# 2_-Input.net
KiCad netlist of a schematic drawn in Altium Designer
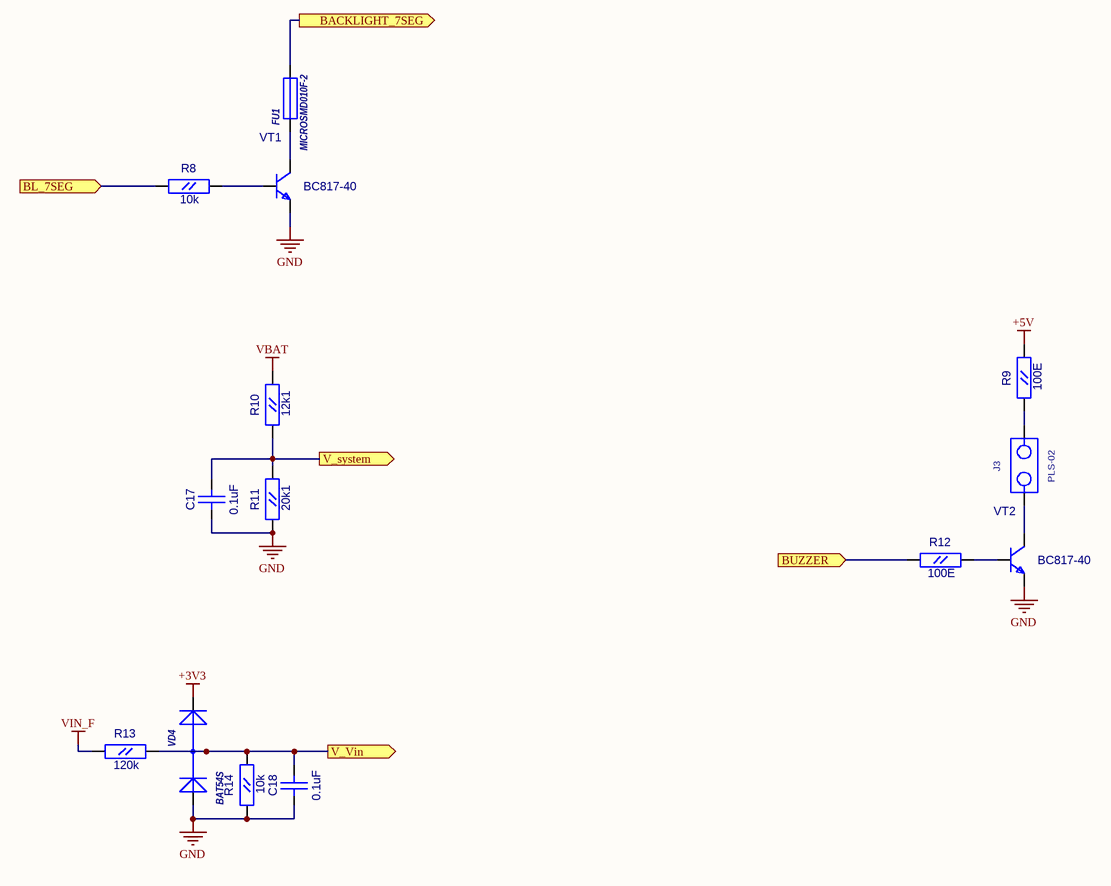
[diagram p0: [2]-Input.SchDoc]

(export (version "E")
  (design (tool "Eeschema 10.0.6"))
  (components
    (comp (ref "C17")
      (value "0.1uF")
      (footprint "CC0603")
      (description "CC0603")
      (libsource (lib "gprs_modem_2") (part "CC0603"))
    )
    (comp (ref "C18")
      (value "0.1uF")
      (footprint "CC0603")
      (description "CC0603")
      (libsource (lib "gprs_modem_2") (part "CC0603"))
    )
    (comp (ref "FU1")
      (value "MICROSMD010F-2")
      (footprint "RC1210")
      (description "MICROSMD")
      (libsource (lib "gprs_modem_2") (part "MICROSMD"))
    )
    (comp (ref "J3") (value "PLS-02") (footprint "PLS-02") (libsource (lib "gprs_modem_2") (part "PLS-02")))
    (comp (ref "R8")
      (value "10k")
      (footprint "RC0603")
      (description "RC0603")
      (libsource (lib "gprs_modem_2") (part "RC0603"))
    )
    (comp (ref "R9")
      (value "100E")
      (footprint "RC0603")
      (description "RC0603")
      (libsource (lib "gprs_modem_2") (part "RC0603"))
    )
    (comp (ref "R10")
      (value "12k1")
      (footprint "RC0603")
      (description "RC0603")
      (libsource (lib "gprs_modem_2") (part "RC0603"))
    )
    (comp (ref "R11")
      (value "20k1")
      (footprint "RC0603")
      (description "RC0603")
      (libsource (lib "gprs_modem_2") (part "RC0603"))
    )
    (comp (ref "R12")
      (value "100E")
      (footprint "RC0603")
      (description "RC0603")
      (libsource (lib "gprs_modem_2") (part "RC0603"))
    )
    (comp (ref "R13")
      (value "120k")
      (footprint "RC0603")
      (description "RC0603")
      (libsource (lib "gprs_modem_2") (part "RC0603"))
    )
    (comp (ref "R14")
      (value "10k")
      (footprint "RC0603")
      (description "RC0603")
      (libsource (lib "gprs_modem_2") (part "RC0603"))
    )
    (comp (ref "VD4")
      (value "BAT54S")
      (footprint "SOT-23(GSD)")
      (description "1.0 Ampere General Purpose Rectifier")
      (libsource (lib "gprs_modem_2") (part "BAT54S"))
    )
    (comp (ref "VT1")
      (value "BC817-40")
      (footprint "SOT-23(123)")
      (description "NPN 500ma transistor")
      (libsource (lib "gprs_modem_2") (part "BC846BLT1"))
    )
    (comp (ref "VT2")
      (value "BC817-40")
      (footprint "SOT-23(123)")
      (description "NPN 500ma transistor")
      (libsource (lib "gprs_modem_2") (part "BC846BLT1"))
    )
  )
  (nets
    (net (code "1") (name "+3V3") (class "Default")
      (node (ref "VD4") (pin "2") (pinfunction "K_2") (pintype "passive"))
    )
    (net (code "2") (name "+5V") (class "Default")
      (node (ref "R9") (pin "2") (pinfunction "B_2") (pintype "passive"))
    )
    (net (code "3") (name "/BACKLIGHT_7SEG") (class "Default")
      (node (ref "FU1") (pin "2") (pintype "passive"))
    )
    (net (code "4") (name "/BL_7SEG") (class "Default")
      (node (ref "R8") (pin "1") (pinfunction "A_1") (pintype "passive"))
    )
    (net (code "5") (name "/BUZZER") (class "Default")
      (node (ref "R12") (pin "1") (pinfunction "A_1") (pintype "passive"))
    )
    (net (code "6") (name "/V_Vin") (class "Default")
      (node (ref "C18") (pin "2") (pinfunction "B_2") (pintype "passive"))
      (node (ref "R13") (pin "2") (pinfunction "B_2") (pintype "passive"))
      (node (ref "R14") (pin "2") (pinfunction "B_2") (pintype "passive"))
      (node (ref "VD4") (pin "3") (pinfunction "AK_3") (pintype "passive"))
    )
    (net (code "7") (name "/V_system") (class "Default")
      (node (ref "C17") (pin "2") (pinfunction "B_2") (pintype "passive"))
      (node (ref "R10") (pin "1") (pinfunction "A_1") (pintype "passive"))
      (node (ref "R11") (pin "2") (pinfunction "B_2") (pintype "passive"))
    )
    (net (code "8") (name "GND") (class "Default")
      (node (ref "C17") (pin "1") (pinfunction "A_1") (pintype "passive"))
      (node (ref "C18") (pin "1") (pinfunction "A_1") (pintype "passive"))
      (node (ref "R11") (pin "1") (pinfunction "A_1") (pintype "passive"))
      (node (ref "R14") (pin "1") (pinfunction "A_1") (pintype "passive"))
      (node (ref "VD4") (pin "1") (pinfunction "A_1") (pintype "passive"))
      (node (ref "VT1") (pin "2") (pinfunction "E_2") (pintype "passive"))
      (node (ref "VT2") (pin "2") (pinfunction "E_2") (pintype "passive"))
    )
    (net (code "9") (name "Net-(R8-B)") (class "Default")
      (node (ref "R8") (pin "2") (pinfunction "B_2") (pintype "passive"))
      (node (ref "VT1") (pin "1") (pinfunction "B_1") (pintype "passive"))
    )
    (net (code "10") (name "Net-(R9-A)") (class "Default")
      (node (ref "J3") (pin "2") (pintype "passive"))
      (node (ref "R9") (pin "1") (pinfunction "A_1") (pintype "passive"))
    )
    (net (code "11") (name "Net-(R12-B)") (class "Default")
      (node (ref "R12") (pin "2") (pinfunction "B_2") (pintype "passive"))
      (node (ref "VT2") (pin "1") (pinfunction "B_1") (pintype "passive"))
    )
    (net (code "12") (name "Net-(VT1-C)") (class "Default")
      (node (ref "FU1") (pin "1") (pintype "passive"))
      (node (ref "VT1") (pin "3") (pinfunction "C_3") (pintype "passive"))
    )
    (net (code "13") (name "Net-(VT2-C)") (class "Default")
      (node (ref "J3") (pin "1") (pintype "passive"))
      (node (ref "VT2") (pin "3") (pinfunction "C_3") (pintype "passive"))
    )
    (net (code "14") (name "VBAT") (class "Default")
      (node (ref "R10") (pin "2") (pinfunction "B_2") (pintype "passive"))
    )
    (net (code "15") (name "VIN_F") (class "Default")
      (node (ref "R13") (pin "1") (pinfunction "A_1") (pintype "passive"))
    )
  )
)
